# PMOD_USB.net
KiCad netlist of a schematic drawn in EAGLE
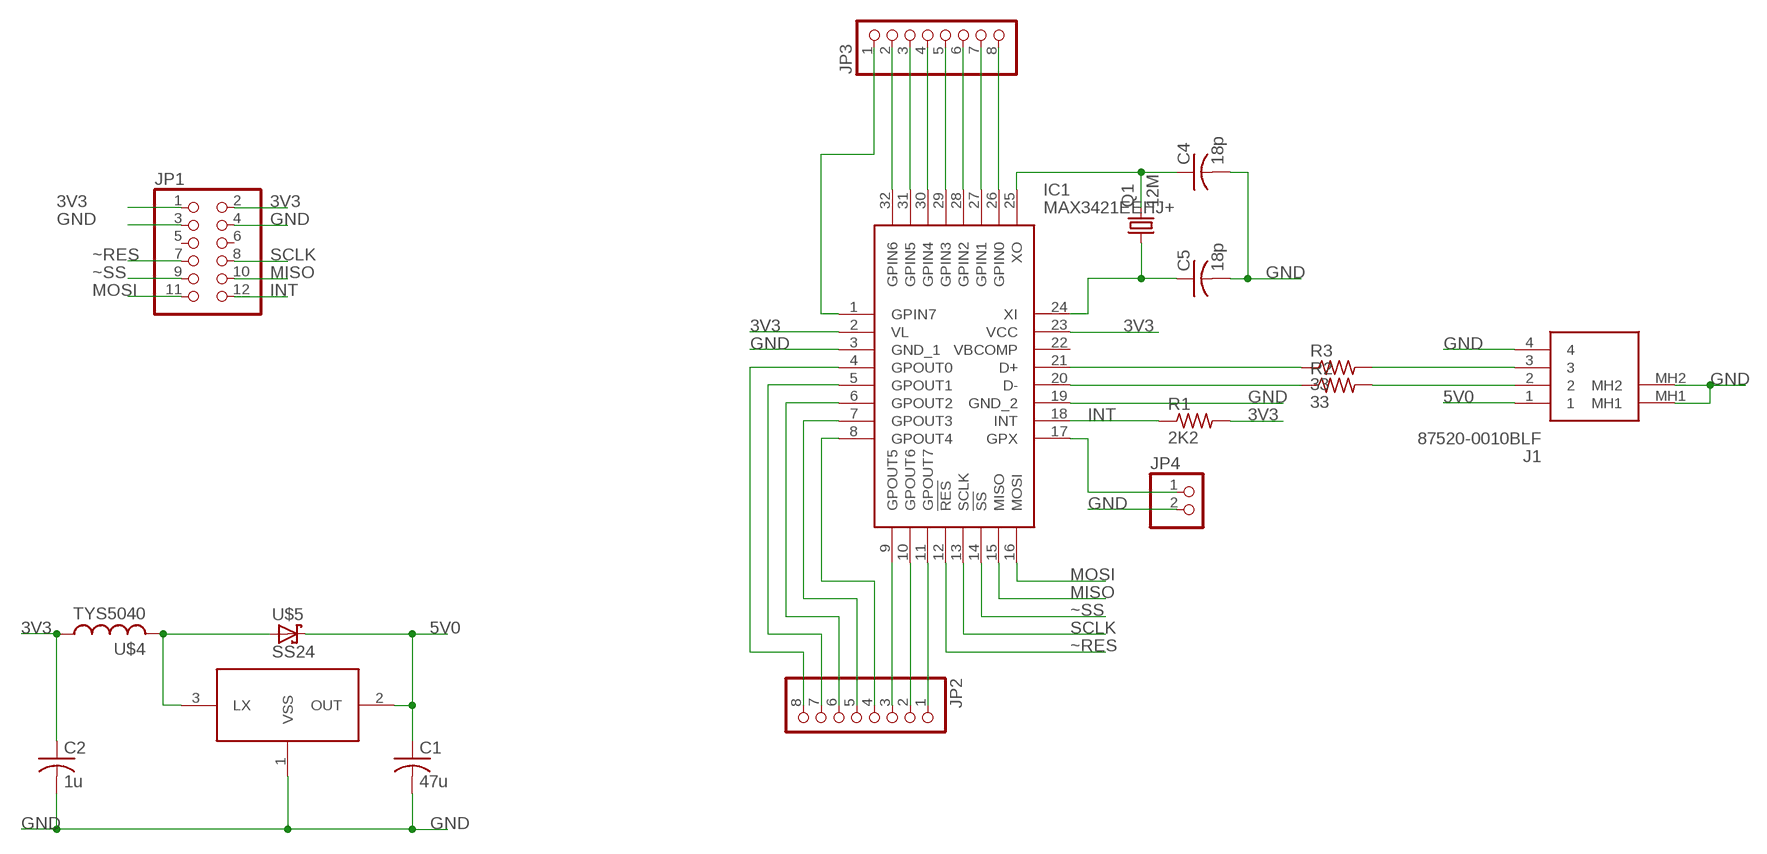
[diagram p0: schematic, sheet 1]

(export (version "E")
  (design (tool "Eeschema 10.0.6"))
  (components
    (comp (ref "C1")
      (value "47u")
      (footprint "eagle-import:C1206K")
      (libsource (lib "eagle-import") (part "C-USC1206K"))
    )
    (comp (ref "C2")
      (value "1u")
      (footprint "eagle-import:C0805K")
      (libsource (lib "eagle-import") (part "C-USC0805K"))
    )
    (comp (ref "C4")
      (value "18p")
      (footprint "eagle-import:C0805")
      (libsource (lib "eagle-import") (part "C-USC0805"))
    )
    (comp (ref "C5")
      (value "18p")
      (footprint "eagle-import:C0805")
      (libsource (lib "eagle-import") (part "C-USC0805"))
    )
    (comp (ref "IC1")
      (value "MAX3421EEHJ+")
      (footprint "eagle-import:QFP50P700X700X120-32N")
      (fields (field (name "MOUSER_PART_NUMBER") "700-MAX3421EEHJ"))
      (libsource (lib "eagle-import") (part "MAX3421EEHJ+"))
    )
    (comp (ref "J1")
      (value "87520-0010BLF")
      (footprint "eagle-import:875200010BLF")
      (fields (field (name "MOUSER_PART_NUMBER") "649-87520-0010BLF"))
      (libsource (lib "eagle-import") (part "87520-0010BLF"))
    )
    (comp (ref "JP1")
      (value "PINHD-2X6/90")
      (footprint "eagle-import:2X06_90")
      (libsource (lib "eagle-import") (part "PINHD-2X6/90"))
    )
    (comp (ref "JP2")
      (value "PINHD-1X8")
      (footprint "eagle-import:1X08")
      (libsource (lib "eagle-import") (part "PINHD-1X8"))
    )
    (comp (ref "JP3")
      (value "PINHD-1X8")
      (footprint "eagle-import:1X08")
      (libsource (lib "eagle-import") (part "PINHD-1X8"))
    )
    (comp (ref "JP4")
      (value "PINHD-1X2")
      (footprint "eagle-import:1X02")
      (libsource (lib "eagle-import") (part "PINHD-1X2"))
    )
    (comp (ref "Q1")
      (value "12M")
      (footprint "eagle-import:HC49_S")
      (libsource (lib "eagle-import") (part "CRYSTALHC49S"))
    )
    (comp (ref "R1")
      (value "2K2")
      (footprint "eagle-import:R0805")
      (libsource (lib "eagle-import") (part "R-US_R0805"))
    )
    (comp (ref "R2")
      (value "33")
      (footprint "eagle-import:R0805")
      (libsource (lib "eagle-import") (part "R-US_R0805"))
    )
    (comp (ref "R3")
      (value "33")
      (footprint "eagle-import:R0805")
      (libsource (lib "eagle-import") (part "R-US_R0805"))
    )
    (comp (ref "U$4")
      (value "TYS5040")
      (footprint "eagle-import:TYS5040")
      (libsource (lib "eagle-import") (part "TYS5040"))
    )
    (comp (ref "U$5")
      (value "SS24")
      (footprint "eagle-import:SMA-DO214AC")
      (libsource (lib "eagle-import") (part "SS24"))
    )
    (comp (ref "U$6")
      (value "ME2108A")
      (footprint "eagle-import:SOT89")
      (libsource (lib "eagle-import") (part "ME2108A"))
    )
  )
  (nets
    (net (code "1") (name "/3V3") (class "Default")
      (node (ref "C2") (pin "1") (pinfunction "1_1") (pintype "passive"))
      (node (ref "IC1") (pin "2") (pinfunction "VL_2") (pintype "bidirectional"))
      (node (ref "IC1") (pin "23") (pinfunction "VCC_23") (pintype "bidirectional"))
      (node (ref "JP1") (pin "1") (pinfunction "1_1") (pintype "passive"))
      (node (ref "JP1") (pin "2") (pinfunction "2_2") (pintype "passive"))
      (node (ref "R1") (pin "2") (pinfunction "2_2") (pintype "passive"))
      (node (ref "U$4") (pin "P$1") (pinfunction "1_P$1") (pintype "passive"))
    )
    (net (code "2") (name "/5V0") (class "Default")
      (node (ref "C1") (pin "1") (pinfunction "1_1") (pintype "passive"))
      (node (ref "J1") (pin "1") (pinfunction "1_1") (pintype "bidirectional"))
      (node (ref "U$5") (pin "K") (pinfunction "C_K") (pintype "passive"))
      (node (ref "U$6") (pin "2") (pinfunction "OUT_2") (pintype "bidirectional"))
    )
    (net (code "3") (name "/GND") (class "Default")
      (node (ref "C1") (pin "2") (pinfunction "2_2") (pintype "passive"))
      (node (ref "C2") (pin "2") (pinfunction "2_2") (pintype "passive"))
      (node (ref "C4") (pin "2") (pinfunction "2_2") (pintype "passive"))
      (node (ref "C5") (pin "2") (pinfunction "2_2") (pintype "passive"))
      (node (ref "IC1") (pin "19") (pinfunction "GND_2_19") (pintype "bidirectional"))
      (node (ref "IC1") (pin "3") (pinfunction "GND_1_3") (pintype "bidirectional"))
      (node (ref "J1") (pin "4") (pinfunction "4_4") (pintype "bidirectional"))
      (node (ref "J1") (pin "MH1") (pinfunction "MH1_MH1") (pintype "bidirectional"))
      (node (ref "J1") (pin "MH2") (pinfunction "MH2_MH2") (pintype "bidirectional"))
      (node (ref "JP1") (pin "3") (pinfunction "3_3") (pintype "passive"))
      (node (ref "JP1") (pin "4") (pinfunction "4_4") (pintype "passive"))
      (node (ref "JP4") (pin "2") (pinfunction "2_2") (pintype "passive"))
      (node (ref "U$6") (pin "1") (pinfunction "VSS_1") (pintype "bidirectional"))
    )
    (net (code "4") (name "/INT") (class "Default")
      (node (ref "IC1") (pin "18") (pinfunction "INT_18") (pintype "bidirectional"))
      (node (ref "JP1") (pin "12") (pinfunction "12_12") (pintype "passive"))
      (node (ref "R1") (pin "1") (pinfunction "1_1") (pintype "passive"))
    )
    (net (code "5") (name "/MISO") (class "Default")
      (node (ref "IC1") (pin "15") (pinfunction "MISO_15") (pintype "bidirectional"))
      (node (ref "JP1") (pin "10") (pinfunction "10_10") (pintype "passive"))
    )
    (net (code "6") (name "/MOSI") (class "Default")
      (node (ref "IC1") (pin "16") (pinfunction "MOSI_16") (pintype "bidirectional"))
      (node (ref "JP1") (pin "11") (pinfunction "11_11") (pintype "passive"))
    )
    (net (code "7") (name "/SCLK") (class "Default")
      (node (ref "IC1") (pin "13") (pinfunction "SCLK_13") (pintype "bidirectional"))
      (node (ref "JP1") (pin "8") (pinfunction "8_8") (pintype "passive"))
    )
    (net (code "8") (name "/~{RES}") (class "Default")
      (node (ref "IC1") (pin "12") (pinfunction "~{RES}_12") (pintype "bidirectional"))
      (node (ref "JP1") (pin "7") (pinfunction "7_7") (pintype "passive"))
    )
    (net (code "9") (name "/~{SS}") (class "Default")
      (node (ref "IC1") (pin "14") (pinfunction "~{SS}_14") (pintype "bidirectional"))
      (node (ref "JP1") (pin "9") (pinfunction "9_9") (pintype "passive"))
    )
    (net (code "10") (name "Net-(IC1-D+)") (class "Default")
      (node (ref "IC1") (pin "21") (pinfunction "D+_21") (pintype "bidirectional"))
      (node (ref "R3") (pin "1") (pinfunction "1_1") (pintype "passive"))
    )
    (net (code "11") (name "Net-(IC1-D-)") (class "Default")
      (node (ref "IC1") (pin "20") (pinfunction "D-_20") (pintype "bidirectional"))
      (node (ref "R2") (pin "1") (pinfunction "1_1") (pintype "passive"))
    )
    (net (code "12") (name "Net-(IC1-GPIN0)") (class "Default")
      (node (ref "IC1") (pin "26") (pinfunction "GPIN0_26") (pintype "bidirectional"))
      (node (ref "JP3") (pin "8") (pinfunction "8_8") (pintype "passive"))
    )
    (net (code "13") (name "Net-(IC1-GPIN1)") (class "Default")
      (node (ref "IC1") (pin "27") (pinfunction "GPIN1_27") (pintype "bidirectional"))
      (node (ref "JP3") (pin "7") (pinfunction "7_7") (pintype "passive"))
    )
    (net (code "14") (name "Net-(IC1-GPIN2)") (class "Default")
      (node (ref "IC1") (pin "28") (pinfunction "GPIN2_28") (pintype "bidirectional"))
      (node (ref "JP3") (pin "6") (pinfunction "6_6") (pintype "passive"))
    )
    (net (code "15") (name "Net-(IC1-GPIN3)") (class "Default")
      (node (ref "IC1") (pin "29") (pinfunction "GPIN3_29") (pintype "bidirectional"))
      (node (ref "JP3") (pin "5") (pinfunction "5_5") (pintype "passive"))
    )
    (net (code "16") (name "Net-(IC1-GPIN4)") (class "Default")
      (node (ref "IC1") (pin "30") (pinfunction "GPIN4_30") (pintype "bidirectional"))
      (node (ref "JP3") (pin "4") (pinfunction "4_4") (pintype "passive"))
    )
    (net (code "17") (name "Net-(IC1-GPIN5)") (class "Default")
      (node (ref "IC1") (pin "31") (pinfunction "GPIN5_31") (pintype "bidirectional"))
      (node (ref "JP3") (pin "3") (pinfunction "3_3") (pintype "passive"))
    )
    (net (code "18") (name "Net-(IC1-GPIN6)") (class "Default")
      (node (ref "IC1") (pin "32") (pinfunction "GPIN6_32") (pintype "bidirectional"))
      (node (ref "JP3") (pin "2") (pinfunction "2_2") (pintype "passive"))
    )
    (net (code "19") (name "Net-(IC1-GPIN7)") (class "Default")
      (node (ref "IC1") (pin "1") (pinfunction "GPIN7_1") (pintype "bidirectional"))
      (node (ref "JP3") (pin "1") (pinfunction "1_1") (pintype "passive"))
    )
    (net (code "20") (name "Net-(IC1-GPOUT0)") (class "Default")
      (node (ref "IC1") (pin "4") (pinfunction "GPOUT0_4") (pintype "bidirectional"))
      (node (ref "JP2") (pin "8") (pinfunction "8_8") (pintype "passive"))
    )
    (net (code "21") (name "Net-(IC1-GPOUT1)") (class "Default")
      (node (ref "IC1") (pin "5") (pinfunction "GPOUT1_5") (pintype "bidirectional"))
      (node (ref "JP2") (pin "7") (pinfunction "7_7") (pintype "passive"))
    )
    (net (code "22") (name "Net-(IC1-GPOUT2)") (class "Default")
      (node (ref "IC1") (pin "6") (pinfunction "GPOUT2_6") (pintype "bidirectional"))
      (node (ref "JP2") (pin "6") (pinfunction "6_6") (pintype "passive"))
    )
    (net (code "23") (name "Net-(IC1-GPOUT3)") (class "Default")
      (node (ref "IC1") (pin "7") (pinfunction "GPOUT3_7") (pintype "bidirectional"))
      (node (ref "JP2") (pin "5") (pinfunction "5_5") (pintype "passive"))
    )
    (net (code "24") (name "Net-(IC1-GPOUT4)") (class "Default")
      (node (ref "IC1") (pin "8") (pinfunction "GPOUT4_8") (pintype "bidirectional"))
      (node (ref "JP2") (pin "4") (pinfunction "4_4") (pintype "passive"))
    )
    (net (code "25") (name "Net-(IC1-GPOUT5)") (class "Default")
      (node (ref "IC1") (pin "9") (pinfunction "GPOUT5_9") (pintype "bidirectional"))
      (node (ref "JP2") (pin "3") (pinfunction "3_3") (pintype "passive"))
    )
    (net (code "26") (name "Net-(IC1-GPOUT6)") (class "Default")
      (node (ref "IC1") (pin "10") (pinfunction "GPOUT6_10") (pintype "bidirectional"))
      (node (ref "JP2") (pin "2") (pinfunction "2_2") (pintype "passive"))
    )
    (net (code "27") (name "Net-(IC1-GPOUT7)") (class "Default")
      (node (ref "IC1") (pin "11") (pinfunction "GPOUT7_11") (pintype "bidirectional"))
      (node (ref "JP2") (pin "1") (pinfunction "1_1") (pintype "passive"))
    )
    (net (code "28") (name "Net-(IC1-GPX)") (class "Default")
      (node (ref "IC1") (pin "17") (pinfunction "GPX_17") (pintype "bidirectional"))
      (node (ref "JP4") (pin "1") (pinfunction "1_1") (pintype "passive"))
    )
    (net (code "29") (name "Net-(IC1-XI)") (class "Default")
      (node (ref "C5") (pin "1") (pinfunction "1_1") (pintype "passive"))
      (node (ref "IC1") (pin "24") (pinfunction "XI_24") (pintype "bidirectional"))
      (node (ref "Q1") (pin "1") (pinfunction "1_1") (pintype "passive"))
    )
    (net (code "30") (name "Net-(IC1-XO)") (class "Default")
      (node (ref "C4") (pin "1") (pinfunction "1_1") (pintype "passive"))
      (node (ref "IC1") (pin "25") (pinfunction "XO_25") (pintype "bidirectional"))
      (node (ref "Q1") (pin "2") (pinfunction "2_2") (pintype "passive"))
    )
    (net (code "31") (name "Net-(J1-Pad2)") (class "Default")
      (node (ref "J1") (pin "2") (pinfunction "2_2") (pintype "bidirectional"))
      (node (ref "R2") (pin "2") (pinfunction "2_2") (pintype "passive"))
    )
    (net (code "32") (name "Net-(J1-Pad3)") (class "Default")
      (node (ref "J1") (pin "3") (pinfunction "3_3") (pintype "bidirectional"))
      (node (ref "R3") (pin "2") (pinfunction "2_2") (pintype "passive"))
    )
    (net (code "33") (name "Net-(U$4-2)") (class "Default")
      (node (ref "U$4") (pin "P$2") (pinfunction "2_P$2") (pintype "passive"))
      (node (ref "U$5") (pin "A") (pinfunction "A_A") (pintype "passive"))
      (node (ref "U$6") (pin "3") (pinfunction "LX_3") (pintype "bidirectional"))
    )
    (net (code "34") (name "unconnected-(IC1-VBCOMP-Pad22)") (class "Default")
      (node (ref "IC1") (pin "22") (pinfunction "VBCOMP_22") (pintype "bidirectional"))
    )
    (net (code "35") (name "unconnected-(JP1-Pad5)") (class "Default")
      (node (ref "JP1") (pin "5") (pinfunction "5_5") (pintype "passive"))
    )
    (net (code "36") (name "unconnected-(JP1-Pad6)") (class "Default")
      (node (ref "JP1") (pin "6") (pinfunction "6_6") (pintype "passive"))
    )
  )
)
